# Relays.net
KiCad netlist of a schematic drawn in Altium Designer
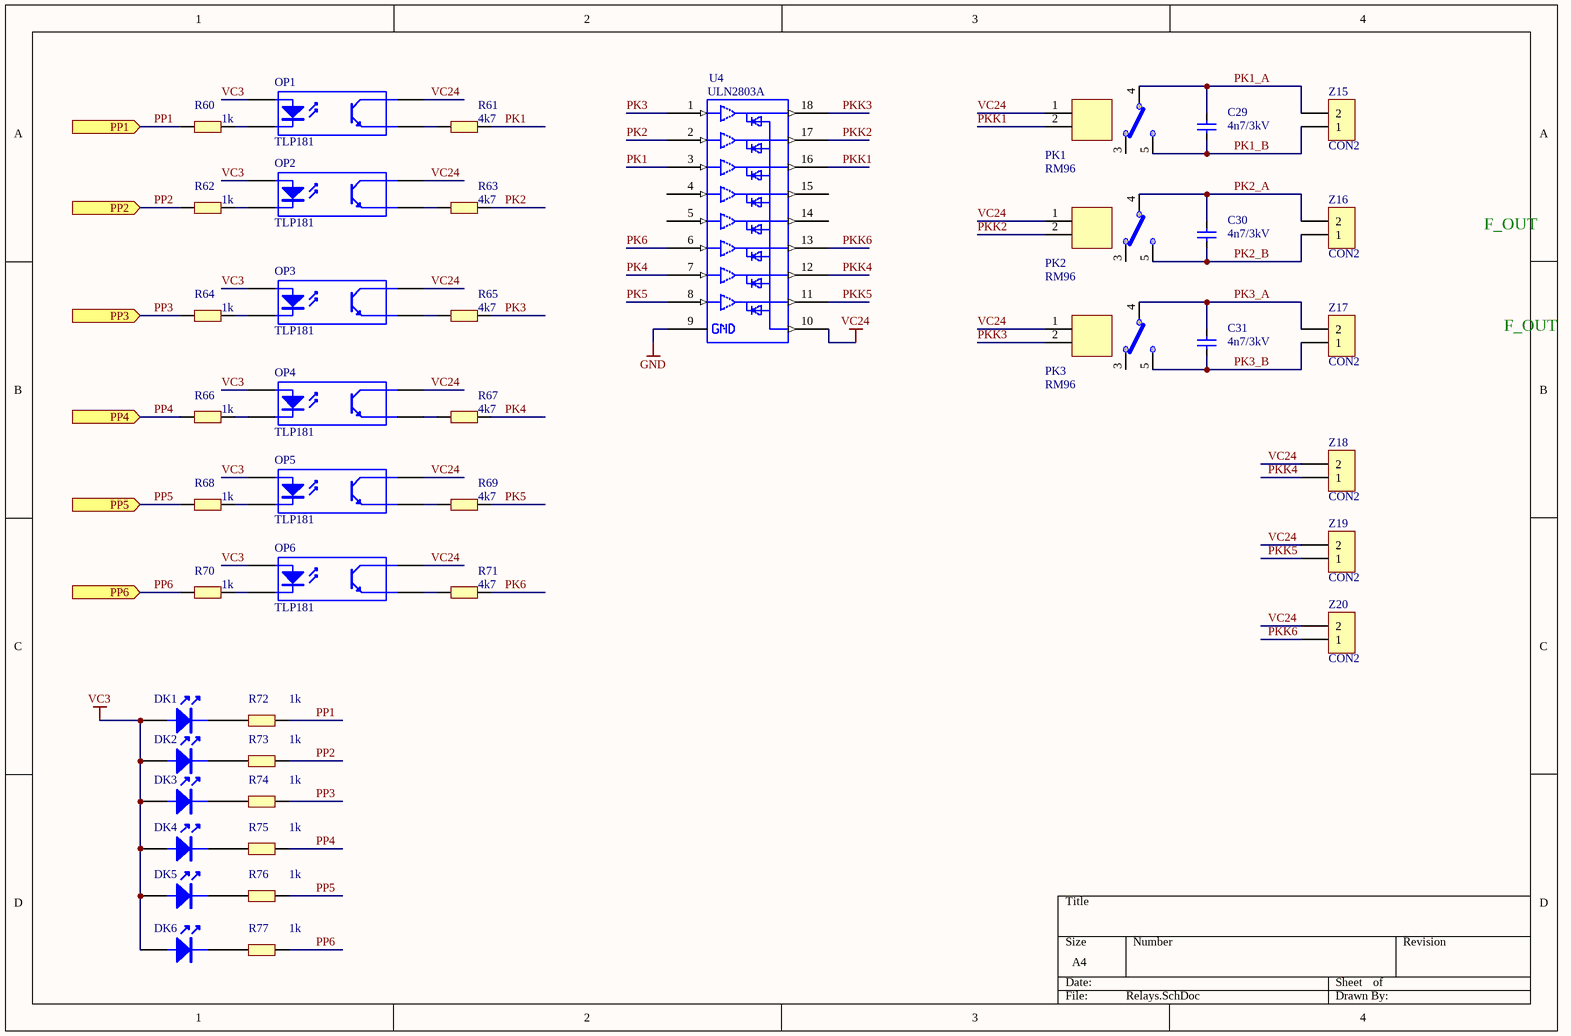
[diagram p0: Relays.SchDoc]

(export (version "E")
  (design (tool "Eeschema 10.0.6"))
  (components
    (comp (ref "C29") (value "4n7/3kV") (footprint "CAP_75") (libsource (lib "*") (part "CAP")))
    (comp (ref "C30") (value "4n7/3kV") (footprint "CAP_75") (libsource (lib "*") (part "CAP")))
    (comp (ref "C31") (value "4n7/3kV") (footprint "CAP_75") (libsource (lib "*") (part "CAP")))
    (comp (ref "DK1") (value "~") (footprint "0805LR") (libsource (lib "*") (part "LED")))
    (comp (ref "DK2") (value "~") (footprint "0805LR") (libsource (lib "*") (part "LED")))
    (comp (ref "DK3") (value "~") (footprint "0805LR") (libsource (lib "*") (part "LED")))
    (comp (ref "DK4") (value "~") (footprint "0805LR") (libsource (lib "*") (part "LED")))
    (comp (ref "DK5") (value "~") (footprint "0805LR") (libsource (lib "*") (part "LED")))
    (comp (ref "DK6") (value "~") (footprint "0805LR") (libsource (lib "*") (part "LED")))
    (comp (ref "OP1")
      (value "TLP181")
      (footprint "TLP181_1")
      (description "Optoisolator")
      (libsource (lib "*") (part "TLP621"))
    )
    (comp (ref "OP2")
      (value "TLP181")
      (footprint "TLP181_1")
      (description "Optoisolator")
      (libsource (lib "*") (part "TLP621"))
    )
    (comp (ref "OP3")
      (value "TLP181")
      (footprint "TLP181_1")
      (description "Optoisolator")
      (libsource (lib "*") (part "TLP621"))
    )
    (comp (ref "OP4")
      (value "TLP181")
      (footprint "TLP181_1")
      (description "Optoisolator")
      (libsource (lib "*") (part "TLP621"))
    )
    (comp (ref "OP5")
      (value "TLP181")
      (footprint "TLP181_1")
      (description "Optoisolator")
      (libsource (lib "*") (part "TLP621"))
    )
    (comp (ref "OP6")
      (value "TLP181")
      (footprint "TLP181_1")
      (description "Optoisolator")
      (libsource (lib "*") (part "TLP621"))
    )
    (comp (ref "PK1") (value "RM96") (footprint "RM96A") (libsource (lib "*") (part "RM96")))
    (comp (ref "PK2") (value "RM96") (footprint "RM96A") (libsource (lib "*") (part "RM96")))
    (comp (ref "PK3") (value "RM96") (footprint "RM96A") (libsource (lib "*") (part "RM96")))
    (comp (ref "R60") (value "1k") (footprint "0805R") (libsource (lib "*") (part "RES3")))
    (comp (ref "R61") (value "4k7") (footprint "0805R") (libsource (lib "*") (part "RES3")))
    (comp (ref "R62") (value "1k") (footprint "0805R") (libsource (lib "*") (part "RES3")))
    (comp (ref "R63") (value "4k7") (footprint "0805R") (libsource (lib "*") (part "RES3")))
    (comp (ref "R64") (value "1k") (footprint "0805R") (libsource (lib "*") (part "RES3")))
    (comp (ref "R65") (value "4k7") (footprint "0805R") (libsource (lib "*") (part "RES3")))
    (comp (ref "R66") (value "1k") (footprint "0805R") (libsource (lib "*") (part "RES3")))
    (comp (ref "R67") (value "4k7") (footprint "0805R") (libsource (lib "*") (part "RES3")))
    (comp (ref "R68") (value "1k") (footprint "0805R") (libsource (lib "*") (part "RES3")))
    (comp (ref "R69") (value "4k7") (footprint "0805R") (libsource (lib "*") (part "RES3")))
    (comp (ref "R70") (value "1k") (footprint "0805R") (libsource (lib "*") (part "RES3")))
    (comp (ref "R71") (value "4k7") (footprint "0805R") (libsource (lib "*") (part "RES3")))
    (comp (ref "R72") (value "1k") (footprint "0805R") (libsource (lib "*") (part "RES3")))
    (comp (ref "R73") (value "1k") (footprint "0805R") (libsource (lib "*") (part "RES3")))
    (comp (ref "R74") (value "1k") (footprint "0805R") (libsource (lib "*") (part "RES3")))
    (comp (ref "R75") (value "1k") (footprint "0805R") (libsource (lib "*") (part "RES3")))
    (comp (ref "R76") (value "1k") (footprint "0805R") (libsource (lib "*") (part "RES3")))
    (comp (ref "R77") (value "1k") (footprint "0805R") (libsource (lib "*") (part "RES3")))
    (comp (ref "U4")
      (value "ULN2803A")
      (footprint "SO-18")
      (libsource (lib "*") (part "Pro31.tmp_ULN2803A_42"))
    )
    (comp (ref "Z15")
      (value "CON2")
      (footprint "ARC-L-2-5.08")
      (description "Connector")
      (libsource (lib "*") (part "CON2"))
    )
    (comp (ref "Z16")
      (value "CON2")
      (footprint "ARC-L-2-5.08")
      (description "Connector")
      (libsource (lib "*") (part "CON2"))
    )
    (comp (ref "Z17")
      (value "CON2")
      (footprint "ARC-L-2-5.08")
      (description "Connector")
      (libsource (lib "*") (part "CON2"))
    )
    (comp (ref "Z18")
      (value "CON2")
      (footprint "ARC-L-2-5.08")
      (description "Connector")
      (libsource (lib "*") (part "CON2"))
    )
    (comp (ref "Z19")
      (value "CON2")
      (footprint "ARC-L-2-5.08")
      (description "Connector")
      (libsource (lib "*") (part "CON2"))
    )
    (comp (ref "Z20")
      (value "CON2")
      (footprint "ARC-L-2-5.08")
      (description "Connector")
      (libsource (lib "*") (part "CON2"))
    )
  )
  (nets
    (net (code "1") (name "/PK1") (class "Default")
      (node (ref "R61") (pin "2") (pintype "passive"))
      (node (ref "U4") (pin "3") (pintype "input"))
    )
    (net (code "2") (name "/PK1_A") (class "Default")
      (node (ref "C29") (pin "2") (pintype "passive"))
      (node (ref "PK1") (pin "4") (pintype "passive"))
      (node (ref "Z15") (pin "2") (pinfunction "2_2") (pintype "passive"))
    )
    (net (code "3") (name "/PK1_B") (class "Default")
      (node (ref "C29") (pin "1") (pintype "passive"))
      (node (ref "PK1") (pin "5") (pintype "passive"))
      (node (ref "Z15") (pin "1") (pinfunction "1_1") (pintype "passive"))
    )
    (net (code "4") (name "/PK2") (class "Default")
      (node (ref "R63") (pin "2") (pintype "passive"))
      (node (ref "U4") (pin "2") (pintype "input"))
    )
    (net (code "5") (name "/PK2_A") (class "Default")
      (node (ref "C30") (pin "2") (pintype "passive"))
      (node (ref "PK2") (pin "4") (pintype "passive"))
      (node (ref "Z16") (pin "2") (pinfunction "2_2") (pintype "passive"))
    )
    (net (code "6") (name "/PK2_B") (class "Default")
      (node (ref "C30") (pin "1") (pintype "passive"))
      (node (ref "PK2") (pin "5") (pintype "passive"))
      (node (ref "Z16") (pin "1") (pinfunction "1_1") (pintype "passive"))
    )
    (net (code "7") (name "/PK3") (class "Default")
      (node (ref "R65") (pin "2") (pintype "passive"))
      (node (ref "U4") (pin "1") (pintype "input"))
    )
    (net (code "8") (name "/PK3_A") (class "Default")
      (node (ref "C31") (pin "2") (pintype "passive"))
      (node (ref "PK3") (pin "4") (pintype "passive"))
      (node (ref "Z17") (pin "2") (pinfunction "2_2") (pintype "passive"))
    )
    (net (code "9") (name "/PK3_B") (class "Default")
      (node (ref "C31") (pin "1") (pintype "passive"))
      (node (ref "PK3") (pin "5") (pintype "passive"))
      (node (ref "Z17") (pin "1") (pinfunction "1_1") (pintype "passive"))
    )
    (net (code "10") (name "/PK4") (class "Default")
      (node (ref "R67") (pin "2") (pintype "passive"))
      (node (ref "U4") (pin "7") (pintype "input"))
    )
    (net (code "11") (name "/PK5") (class "Default")
      (node (ref "R69") (pin "2") (pintype "passive"))
      (node (ref "U4") (pin "8") (pintype "input"))
    )
    (net (code "12") (name "/PK6") (class "Default")
      (node (ref "R71") (pin "2") (pintype "passive"))
      (node (ref "U4") (pin "6") (pintype "input"))
    )
    (net (code "13") (name "/PKK1") (class "Default")
      (node (ref "PK1") (pin "2") (pintype "passive"))
      (node (ref "U4") (pin "16") (pintype "output"))
    )
    (net (code "14") (name "/PKK2") (class "Default")
      (node (ref "PK2") (pin "2") (pintype "passive"))
      (node (ref "U4") (pin "17") (pintype "output"))
    )
    (net (code "15") (name "/PKK3") (class "Default")
      (node (ref "PK3") (pin "2") (pintype "passive"))
      (node (ref "U4") (pin "18") (pintype "output"))
    )
    (net (code "16") (name "/PKK4") (class "Default")
      (node (ref "U4") (pin "12") (pintype "output"))
      (node (ref "Z18") (pin "1") (pinfunction "1_1") (pintype "passive"))
    )
    (net (code "17") (name "/PKK5") (class "Default")
      (node (ref "U4") (pin "11") (pintype "output"))
      (node (ref "Z19") (pin "1") (pinfunction "1_1") (pintype "passive"))
    )
    (net (code "18") (name "/PKK6") (class "Default")
      (node (ref "U4") (pin "13") (pintype "output"))
      (node (ref "Z20") (pin "1") (pinfunction "1_1") (pintype "passive"))
    )
    (net (code "19") (name "/PP1") (class "Default")
      (node (ref "R60") (pin "1") (pintype "passive"))
      (node (ref "R72") (pin "2") (pintype "passive"))
    )
    (net (code "20") (name "/PP2") (class "Default")
      (node (ref "R62") (pin "1") (pintype "passive"))
      (node (ref "R73") (pin "2") (pintype "passive"))
    )
    (net (code "21") (name "/PP3") (class "Default")
      (node (ref "R64") (pin "1") (pintype "passive"))
      (node (ref "R74") (pin "2") (pintype "passive"))
    )
    (net (code "22") (name "/PP4") (class "Default")
      (node (ref "R66") (pin "1") (pintype "passive"))
      (node (ref "R75") (pin "2") (pintype "passive"))
    )
    (net (code "23") (name "/PP5") (class "Default")
      (node (ref "R68") (pin "1") (pintype "passive"))
      (node (ref "R76") (pin "2") (pintype "passive"))
    )
    (net (code "24") (name "/PP6") (class "Default")
      (node (ref "R70") (pin "1") (pintype "passive"))
      (node (ref "R77") (pin "2") (pintype "passive"))
    )
    (net (code "25") (name "GND") (class "Default") (node (ref "U4") (pin "9") (pintype "passive")))
    (net (code "26") (name "Net-(DK1-2)") (class "Default")
      (node (ref "DK1") (pin "K") (pinfunction "2_K") (pintype "passive"))
      (node (ref "R72") (pin "1") (pintype "passive"))
    )
    (net (code "27") (name "Net-(DK2-2)") (class "Default")
      (node (ref "DK2") (pin "K") (pinfunction "2_K") (pintype "passive"))
      (node (ref "R73") (pin "1") (pintype "passive"))
    )
    (net (code "28") (name "Net-(DK3-2)") (class "Default")
      (node (ref "DK3") (pin "K") (pinfunction "2_K") (pintype "passive"))
      (node (ref "R74") (pin "1") (pintype "passive"))
    )
    (net (code "29") (name "Net-(DK4-2)") (class "Default")
      (node (ref "DK4") (pin "K") (pinfunction "2_K") (pintype "passive"))
      (node (ref "R75") (pin "1") (pintype "passive"))
    )
    (net (code "30") (name "Net-(DK5-2)") (class "Default")
      (node (ref "DK5") (pin "K") (pinfunction "2_K") (pintype "passive"))
      (node (ref "R76") (pin "1") (pintype "passive"))
    )
    (net (code "31") (name "Net-(DK6-2)") (class "Default")
      (node (ref "DK6") (pin "K") (pinfunction "2_K") (pintype "passive"))
      (node (ref "R77") (pin "1") (pintype "passive"))
    )
    (net (code "32") (name "Net-(OP1-4)") (class "Default")
      (node (ref "OP1") (pin "3") (pinfunction "4_3") (pintype "passive"))
      (node (ref "R61") (pin "1") (pintype "passive"))
    )
    (net (code "33") (name "Net-(OP1-Pad2)") (class "Default")
      (node (ref "OP1") (pin "2") (pinfunction "2_2") (pintype "passive"))
      (node (ref "R60") (pin "2") (pintype "passive"))
    )
    (net (code "34") (name "Net-(OP2-4)") (class "Default")
      (node (ref "OP2") (pin "3") (pinfunction "4_3") (pintype "passive"))
      (node (ref "R63") (pin "1") (pintype "passive"))
    )
    (net (code "35") (name "Net-(OP2-Pad2)") (class "Default")
      (node (ref "OP2") (pin "2") (pinfunction "2_2") (pintype "passive"))
      (node (ref "R62") (pin "2") (pintype "passive"))
    )
    (net (code "36") (name "Net-(OP3-4)") (class "Default")
      (node (ref "OP3") (pin "3") (pinfunction "4_3") (pintype "passive"))
      (node (ref "R65") (pin "1") (pintype "passive"))
    )
    (net (code "37") (name "Net-(OP3-Pad2)") (class "Default")
      (node (ref "OP3") (pin "2") (pinfunction "2_2") (pintype "passive"))
      (node (ref "R64") (pin "2") (pintype "passive"))
    )
    (net (code "38") (name "Net-(OP4-4)") (class "Default")
      (node (ref "OP4") (pin "3") (pinfunction "4_3") (pintype "passive"))
      (node (ref "R67") (pin "1") (pintype "passive"))
    )
    (net (code "39") (name "Net-(OP4-Pad2)") (class "Default")
      (node (ref "OP4") (pin "2") (pinfunction "2_2") (pintype "passive"))
      (node (ref "R66") (pin "2") (pintype "passive"))
    )
    (net (code "40") (name "Net-(OP5-4)") (class "Default")
      (node (ref "OP5") (pin "3") (pinfunction "4_3") (pintype "passive"))
      (node (ref "R69") (pin "1") (pintype "passive"))
    )
    (net (code "41") (name "Net-(OP5-Pad2)") (class "Default")
      (node (ref "OP5") (pin "2") (pinfunction "2_2") (pintype "passive"))
      (node (ref "R68") (pin "2") (pintype "passive"))
    )
    (net (code "42") (name "Net-(OP6-4)") (class "Default")
      (node (ref "OP6") (pin "3") (pinfunction "4_3") (pintype "passive"))
      (node (ref "R71") (pin "1") (pintype "passive"))
    )
    (net (code "43") (name "Net-(OP6-Pad2)") (class "Default")
      (node (ref "OP6") (pin "2") (pinfunction "2_2") (pintype "passive"))
      (node (ref "R70") (pin "2") (pintype "passive"))
    )
    (net (code "44") (name "VC3") (class "Default")
      (node (ref "DK1") (pin "A") (pinfunction "1_A") (pintype "passive"))
      (node (ref "DK2") (pin "A") (pinfunction "1_A") (pintype "passive"))
      (node (ref "DK3") (pin "A") (pinfunction "1_A") (pintype "passive"))
      (node (ref "DK4") (pin "A") (pinfunction "1_A") (pintype "passive"))
      (node (ref "DK5") (pin "A") (pinfunction "1_A") (pintype "passive"))
      (node (ref "DK6") (pin "A") (pinfunction "1_A") (pintype "passive"))
      (node (ref "OP1") (pin "1") (pinfunction "1_1") (pintype "passive"))
      (node (ref "OP2") (pin "1") (pinfunction "1_1") (pintype "passive"))
      (node (ref "OP3") (pin "1") (pinfunction "1_1") (pintype "passive"))
      (node (ref "OP4") (pin "1") (pinfunction "1_1") (pintype "passive"))
      (node (ref "OP5") (pin "1") (pinfunction "1_1") (pintype "passive"))
      (node (ref "OP6") (pin "1") (pinfunction "1_1") (pintype "passive"))
    )
    (net (code "45") (name "VC24") (class "Default")
      (node (ref "OP1") (pin "4") (pinfunction "3_4") (pintype "passive"))
      (node (ref "OP2") (pin "4") (pinfunction "3_4") (pintype "passive"))
      (node (ref "OP3") (pin "4") (pinfunction "3_4") (pintype "passive"))
      (node (ref "OP4") (pin "4") (pinfunction "3_4") (pintype "passive"))
      (node (ref "OP5") (pin "4") (pinfunction "3_4") (pintype "passive"))
      (node (ref "OP6") (pin "4") (pinfunction "3_4") (pintype "passive"))
      (node (ref "PK1") (pin "1") (pintype "passive"))
      (node (ref "PK2") (pin "1") (pintype "passive"))
      (node (ref "PK3") (pin "1") (pintype "passive"))
      (node (ref "U4") (pin "10") (pintype "output"))
      (node (ref "Z18") (pin "2") (pinfunction "2_2") (pintype "passive"))
      (node (ref "Z19") (pin "2") (pinfunction "2_2") (pintype "passive"))
      (node (ref "Z20") (pin "2") (pinfunction "2_2") (pintype "passive"))
    )
    (net (code "46") (name "unconnected-(PK1-Pad3)") (class "Default")
      (node (ref "PK1") (pin "3") (pintype "passive"))
    )
    (net (code "47") (name "unconnected-(PK2-Pad3)") (class "Default")
      (node (ref "PK2") (pin "3") (pintype "passive"))
    )
    (net (code "48") (name "unconnected-(PK3-Pad3)") (class "Default")
      (node (ref "PK3") (pin "3") (pintype "passive"))
    )
    (net (code "49") (name "unconnected-(U4-Pad4)") (class "Default")
      (node (ref "U4") (pin "4") (pintype "input"))
    )
    (net (code "50") (name "unconnected-(U4-Pad5)") (class "Default")
      (node (ref "U4") (pin "5") (pintype "input"))
    )
    (net (code "51") (name "unconnected-(U4-Pad14)") (class "Default")
      (node (ref "U4") (pin "14") (pintype "output"))
    )
    (net (code "52") (name "unconnected-(U4-Pad15)") (class "Default")
      (node (ref "U4") (pin "15") (pintype "output"))
    )
  )
)
